# doorbell-hardware.net
KiCad netlist of a schematic drawn in EAGLE
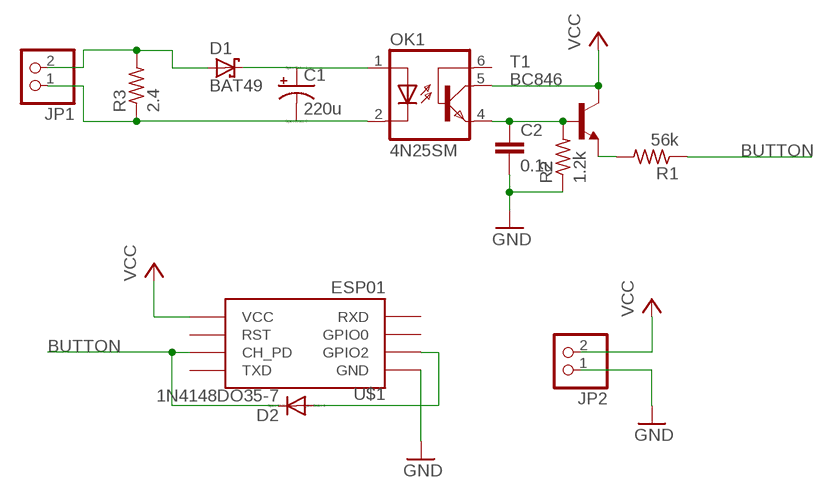
[diagram p0: schematic, sheet 1]

(export (version "E")
  (design (tool "Eeschema 10.0.6"))
  (components
    (comp (ref "C1")
      (value "220u")
      (footprint "eagle-import:E2-4")
      (libsource (lib "eagle-import") (part "CPOL-USE2-4"))
    )
    (comp (ref "C2")
      (value "0.1u")
      (footprint "eagle-import:C2.5-2")
      (libsource (lib "eagle-import") (part "C2.5/2"))
    )
    (comp (ref "D1")
      (value "BAT49")
      (footprint "eagle-import:DO41-10")
      (libsource (lib "eagle-import") (part "BAT49"))
    )
    (comp (ref "D2")
      (value "1N4148DO35-7")
      (footprint "eagle-import:DO35-7")
      (libsource (lib "eagle-import") (part "1N4148DO35-7"))
    )
    (comp (ref "JP1")
      (value "PINHD-1X2")
      (footprint "eagle-import:1X02")
      (libsource (lib "eagle-import") (part "PINHD-1X2"))
    )
    (comp (ref "JP2")
      (value "PINHD-1X2")
      (footprint "eagle-import:1X02")
      (libsource (lib "eagle-import") (part "PINHD-1X2"))
    )
    (comp (ref "OK1")
      (value "4N25SM")
      (footprint "eagle-import:DIL6-SMD")
      (fields (field (name "MF") "FAIRCHILD SEMICONDUCTOR"))
      (libsource (lib "eagle-import") (part "4N?MS25"))
    )
    (comp (ref "R1")
      (value "56k")
      (footprint "eagle-import:0204_5")
      (libsource (lib "eagle-import") (part "R-US_0204/5"))
    )
    (comp (ref "R2")
      (value "1.2k")
      (footprint "eagle-import:0204_5")
      (libsource (lib "eagle-import") (part "R-US_0204/5"))
    )
    (comp (ref "R3")
      (value "2.4")
      (footprint "eagle-import:P0613_15")
      (libsource (lib "eagle-import") (part "R-US_0613/15"))
    )
    (comp (ref "T1")
      (value "BC846")
      (footprint "eagle-import:SOT23")
      (libsource (lib "eagle-import") (part "BC846"))
    )
    (comp (ref "U$1")
      (value "ESP01")
      (footprint "eagle-import:ESP01")
      (libsource (lib "eagle-import") (part "ESP01"))
    )
  )
  (nets
    (net (code "1") (name "/BUTTON") (class "Default")
      (node (ref "D2") (pin "C") (pinfunction "C_C") (pintype "passive"))
      (node (ref "R1") (pin "1") (pinfunction "1_1") (pintype "passive"))
      (node (ref "U$1") (pin "CH_PD") (pinfunction "CH_PD_CH_PD") (pintype "bidirectional"))
    )
    (net (code "2") (name "GND") (class "Default")
      (node (ref "C2") (pin "2") (pinfunction "2_2") (pintype "passive"))
      (node (ref "JP2") (pin "1") (pinfunction "1_1") (pintype "passive"))
      (node (ref "R2") (pin "1") (pinfunction "1_1") (pintype "passive"))
      (node (ref "U$1") (pin "GND") (pinfunction "GND_GND") (pintype "bidirectional"))
    )
    (net (code "3") (name "Net-(D1-PadA)") (class "Default")
      (node (ref "D1") (pin "A") (pinfunction "A_A") (pintype "passive"))
      (node (ref "JP1") (pin "2") (pinfunction "2_2") (pintype "passive"))
      (node (ref "R3") (pin "2") (pinfunction "2_2") (pintype "passive"))
    )
    (net (code "4") (name "Net-(D2-PadA)") (class "Default")
      (node (ref "D2") (pin "A") (pinfunction "A_A") (pintype "passive"))
      (node (ref "U$1") (pin "GPIO2") (pinfunction "GPIO2_GPIO2") (pintype "bidirectional"))
    )
    (net (code "5") (name "Net-(OK1-A)") (class "Default")
      (node (ref "C1") (pin "+") (pinfunction "+_+") (pintype "passive"))
      (node (ref "D1") (pin "C") (pinfunction "C_C") (pintype "passive"))
      (node (ref "OK1") (pin "1") (pinfunction "A_1") (pintype "passive"))
    )
    (net (code "6") (name "Net-(OK1-C)") (class "Default")
      (node (ref "C1") (pin "-") (pinfunction "-_-") (pintype "passive"))
      (node (ref "JP1") (pin "1") (pinfunction "1_1") (pintype "passive"))
      (node (ref "OK1") (pin "2") (pinfunction "C_2") (pintype "passive"))
      (node (ref "R3") (pin "1") (pinfunction "1_1") (pintype "passive"))
    )
    (net (code "7") (name "Net-(OK1-EMI)") (class "Default")
      (node (ref "C2") (pin "1") (pinfunction "1_1") (pintype "passive"))
      (node (ref "OK1") (pin "4") (pinfunction "EMI_4") (pintype "passive"))
      (node (ref "R2") (pin "2") (pinfunction "2_2") (pintype "passive"))
      (node (ref "T1") (pin "1") (pinfunction "B_1") (pintype "passive"))
    )
    (net (code "8") (name "Net-(T1-E)") (class "Default")
      (node (ref "R1") (pin "2") (pinfunction "2_2") (pintype "passive"))
      (node (ref "T1") (pin "2") (pinfunction "E_2") (pintype "passive"))
    )
    (net (code "9") (name "VCC") (class "Default")
      (node (ref "JP2") (pin "2") (pinfunction "2_2") (pintype "passive"))
      (node (ref "OK1") (pin "5") (pinfunction "COL_5") (pintype "passive"))
      (node (ref "T1") (pin "3") (pinfunction "C_3") (pintype "passive"))
      (node (ref "U$1") (pin "VCC") (pinfunction "VCC_VCC") (pintype "bidirectional"))
    )
    (net (code "10") (name "unconnected-(OK1-BAS-Pad6)") (class "Default")
      (node (ref "OK1") (pin "6") (pinfunction "BAS_6") (pintype "passive"))
    )
    (net (code "11") (name "unconnected-(U$1-PadGPIO0)") (class "Default")
      (node (ref "U$1") (pin "GPIO0") (pinfunction "GPIO0_GPIO0") (pintype "bidirectional"))
    )
    (net (code "12") (name "unconnected-(U$1-PadRST)") (class "Default")
      (node (ref "U$1") (pin "RST") (pinfunction "RST_RST") (pintype "bidirectional"))
    )
    (net (code "13") (name "unconnected-(U$1-RXD-PadRX)") (class "Default")
      (node (ref "U$1") (pin "RX") (pinfunction "RXD_RX") (pintype "bidirectional"))
    )
    (net (code "14") (name "unconnected-(U$1-TXD-PadTX)") (class "Default")
      (node (ref "U$1") (pin "TX") (pinfunction "TXD_TX") (pintype "bidirectional"))
    )
  )
)
